# Connector.net
KiCad netlist of a schematic drawn in Altium Designer
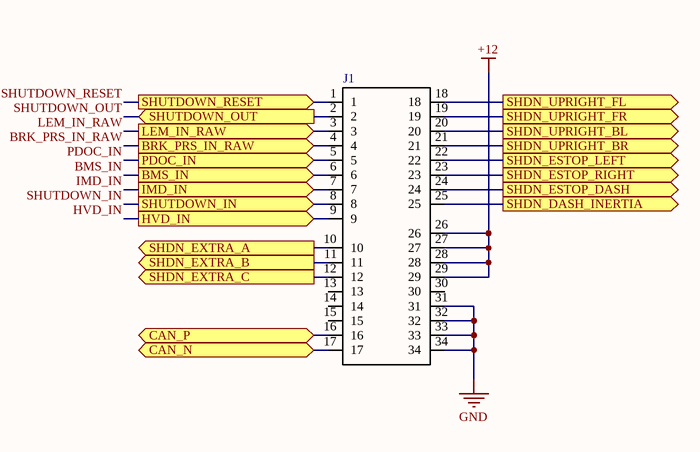
[diagram p0: Connector.SchDoc]

(export (version "E")
  (design (tool "Eeschema 10.0.6"))
  (components
    (comp (ref "J1")
      (value "6437288-2")
      (footprint "TE_6437288-2")
      (description "Conn Wire to Board RCP 34 POS 1.5mm Solder RA Thru-Hole Automotive Tube")
      (fields (field (name "MF") "TE Connectivity") (field (name "DIGI-KEY_PART_NUMBER") "A142477-ND"))
      (libsource (lib "6437288-2") (part "6437288-2"))
    )
  )
  (nets
    (net (code "1") (name "+12") (class "Default")
      (node (ref "J1") (pin "26") (pinfunction "26_26") (pintype "passive"))
      (node (ref "J1") (pin "27") (pinfunction "27_27") (pintype "passive"))
      (node (ref "J1") (pin "28") (pinfunction "28_28") (pintype "passive"))
      (node (ref "J1") (pin "29") (pinfunction "29_29") (pintype "passive"))
    )
    (net (code "2") (name "/BMS_IN") (class "Default")
      (node (ref "J1") (pin "6") (pinfunction "6_6") (pintype "passive"))
    )
    (net (code "3") (name "/BRK_PRS_IN_RAW") (class "Default")
      (node (ref "J1") (pin "4") (pinfunction "4_4") (pintype "passive"))
    )
    (net (code "4") (name "/CAN_N") (class "Default")
      (node (ref "J1") (pin "17") (pinfunction "17_17") (pintype "passive"))
    )
    (net (code "5") (name "/CAN_P") (class "Default")
      (node (ref "J1") (pin "16") (pinfunction "16_16") (pintype "passive"))
    )
    (net (code "6") (name "/HVD_IN") (class "Default")
      (node (ref "J1") (pin "9") (pinfunction "9_9") (pintype "passive"))
    )
    (net (code "7") (name "/IMD_IN") (class "Default")
      (node (ref "J1") (pin "7") (pinfunction "7_7") (pintype "passive"))
    )
    (net (code "8") (name "/LEM_IN_RAW") (class "Default")
      (node (ref "J1") (pin "3") (pinfunction "3_3") (pintype "passive"))
    )
    (net (code "9") (name "/PDOC_IN") (class "Default")
      (node (ref "J1") (pin "5") (pinfunction "5_5") (pintype "passive"))
    )
    (net (code "10") (name "/SHDN_DASH_INERTIA") (class "Default")
      (node (ref "J1") (pin "25") (pinfunction "25_25") (pintype "passive"))
    )
    (net (code "11") (name "/SHDN_ESTOP_DASH") (class "Default")
      (node (ref "J1") (pin "24") (pinfunction "24_24") (pintype "passive"))
    )
    (net (code "12") (name "/SHDN_ESTOP_LEFT") (class "Default")
      (node (ref "J1") (pin "22") (pinfunction "22_22") (pintype "passive"))
    )
    (net (code "13") (name "/SHDN_ESTOP_RIGHT") (class "Default")
      (node (ref "J1") (pin "23") (pinfunction "23_23") (pintype "passive"))
    )
    (net (code "14") (name "/SHDN_EXTRA_A") (class "Default")
      (node (ref "J1") (pin "10") (pinfunction "10_10") (pintype "passive"))
    )
    (net (code "15") (name "/SHDN_EXTRA_B") (class "Default")
      (node (ref "J1") (pin "11") (pinfunction "11_11") (pintype "passive"))
    )
    (net (code "16") (name "/SHDN_EXTRA_C") (class "Default")
      (node (ref "J1") (pin "12") (pinfunction "12_12") (pintype "passive"))
    )
    (net (code "17") (name "/SHDN_UPRIGHT_BL") (class "Default")
      (node (ref "J1") (pin "20") (pinfunction "20_20") (pintype "passive"))
    )
    (net (code "18") (name "/SHDN_UPRIGHT_BR") (class "Default")
      (node (ref "J1") (pin "21") (pinfunction "21_21") (pintype "passive"))
    )
    (net (code "19") (name "/SHDN_UPRIGHT_FL") (class "Default")
      (node (ref "J1") (pin "18") (pinfunction "18_18") (pintype "passive"))
    )
    (net (code "20") (name "/SHDN_UPRIGHT_FR") (class "Default")
      (node (ref "J1") (pin "19") (pinfunction "19_19") (pintype "passive"))
    )
    (net (code "21") (name "/SHUTDOWN_IN") (class "Default")
      (node (ref "J1") (pin "8") (pinfunction "8_8") (pintype "passive"))
    )
    (net (code "22") (name "/SHUTDOWN_OUT") (class "Default")
      (node (ref "J1") (pin "2") (pinfunction "2_2") (pintype "passive"))
    )
    (net (code "23") (name "/SHUTDOWN_RESET") (class "Default")
      (node (ref "J1") (pin "1") (pinfunction "1_1") (pintype "passive"))
    )
    (net (code "24") (name "GND") (class "Default")
      (node (ref "J1") (pin "31") (pinfunction "31_31") (pintype "passive"))
      (node (ref "J1") (pin "32") (pinfunction "32_32") (pintype "passive"))
      (node (ref "J1") (pin "33") (pinfunction "33_33") (pintype "passive"))
      (node (ref "J1") (pin "34") (pinfunction "34_34") (pintype "passive"))
    )
    (net (code "25") (name "unconnected-(J1-Pad13)") (class "Default")
      (node (ref "J1") (pin "13") (pinfunction "13_13") (pintype "passive"))
    )
    (net (code "26") (name "unconnected-(J1-Pad14)") (class "Default")
      (node (ref "J1") (pin "14") (pinfunction "14_14") (pintype "passive"))
    )
    (net (code "27") (name "unconnected-(J1-Pad15)") (class "Default")
      (node (ref "J1") (pin "15") (pinfunction "15_15") (pintype "passive"))
    )
    (net (code "28") (name "unconnected-(J1-Pad30)") (class "Default")
      (node (ref "J1") (pin "30") (pinfunction "30_30") (pintype "passive"))
    )
  )
)
